# ConectoresAdicionales.net
KiCad netlist of a schematic drawn in Altium Designer
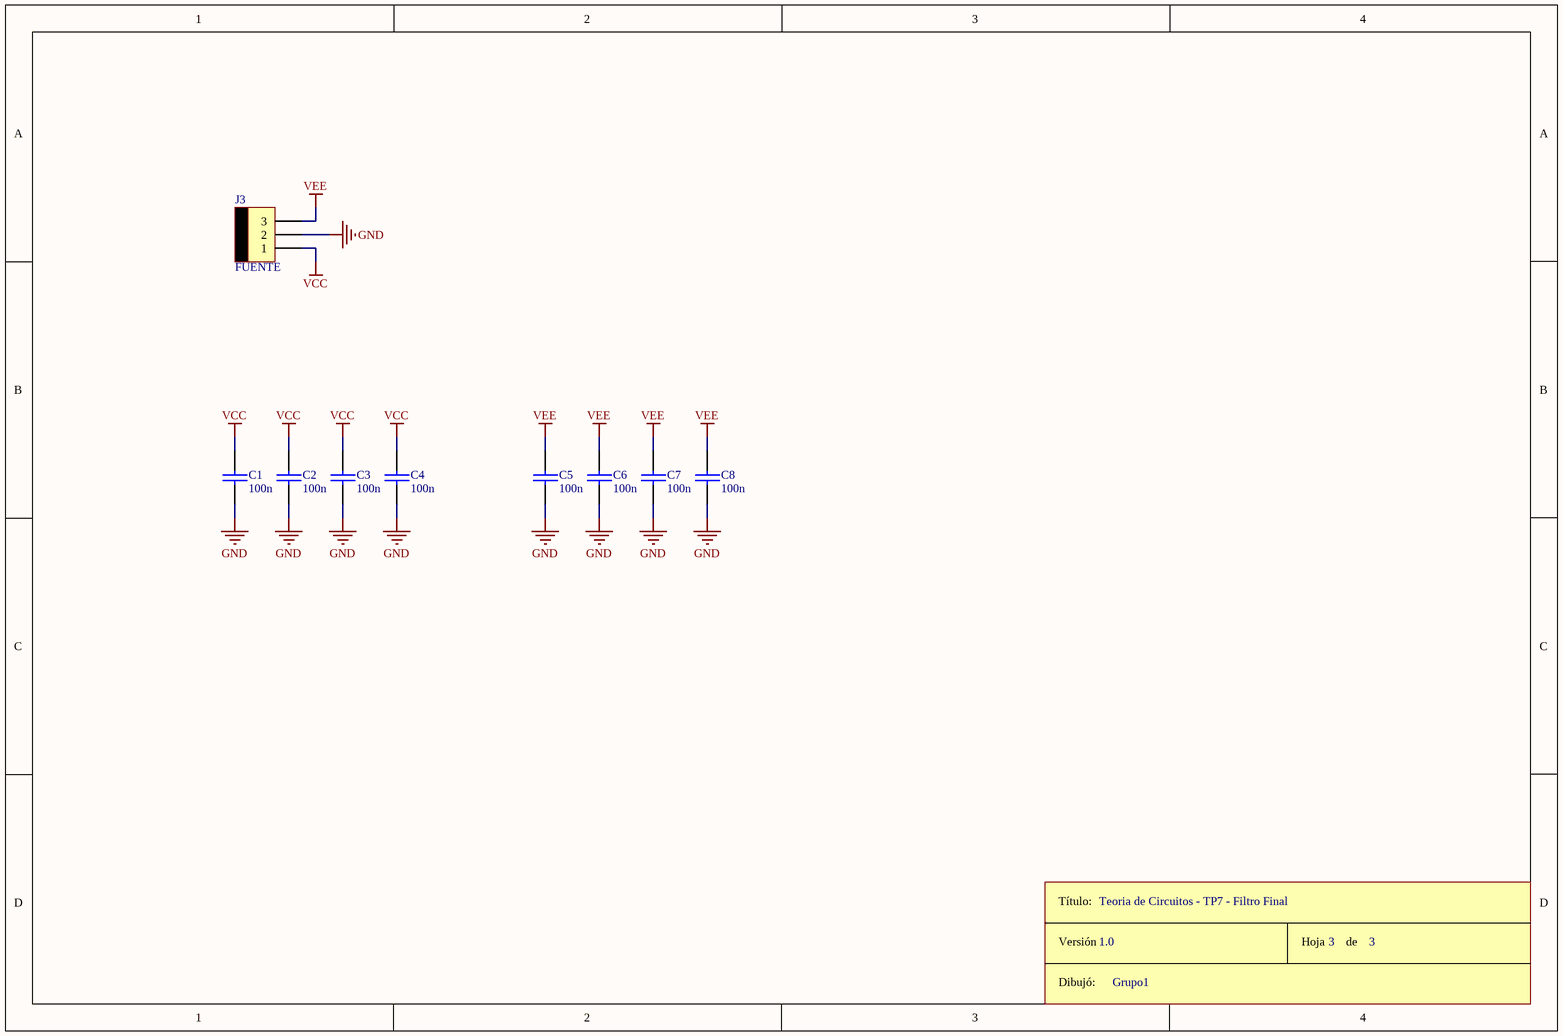
[diagram p0: ConectoresAdicionales.SchDoc]

(export (version "E")
  (design (tool "Eeschema 10.0.6"))
  (components
    (comp (ref "C1") (value "100n") (footprint "CAP100") (libsource (lib "LIB PIO IX") (part "CAP")))
    (comp (ref "C2") (value "100n") (footprint "CAP100") (libsource (lib "LIB PIO IX") (part "CAP")))
    (comp (ref "C3") (value "100n") (footprint "CAP100") (libsource (lib "LIB PIO IX") (part "CAP")))
    (comp (ref "C4") (value "100n") (footprint "CAP100") (libsource (lib "LIB PIO IX") (part "CAP")))
    (comp (ref "C5") (value "100n") (footprint "CAP100") (libsource (lib "LIB PIO IX") (part "CAP")))
    (comp (ref "C6") (value "100n") (footprint "CAP100") (libsource (lib "LIB PIO IX") (part "CAP")))
    (comp (ref "C7") (value "100n") (footprint "CAP100") (libsource (lib "LIB PIO IX") (part "CAP")))
    (comp (ref "C8") (value "100n") (footprint "CAP100") (libsource (lib "LIB PIO IX") (part "CAP")))
    (comp (ref "J3") (value "FUENTE") (footprint "MOLEX3") (libsource (lib "LIB PIO IX") (part "MOLEX3")))
    (comp (ref "ROT3") (value "Rótulo") (libsource (lib "LIB PIO IX") (part "Rótulo")))
  )
  (nets
    (net (code "1") (name "GND") (class "Default")
      (node (ref "C1") (pin "2") (pinfunction "2_2") (pintype "passive"))
      (node (ref "C2") (pin "2") (pinfunction "2_2") (pintype "passive"))
      (node (ref "C3") (pin "2") (pinfunction "2_2") (pintype "passive"))
      (node (ref "C4") (pin "2") (pinfunction "2_2") (pintype "passive"))
      (node (ref "C5") (pin "2") (pinfunction "2_2") (pintype "passive"))
      (node (ref "C6") (pin "2") (pinfunction "2_2") (pintype "passive"))
      (node (ref "C7") (pin "2") (pinfunction "2_2") (pintype "passive"))
      (node (ref "C8") (pin "2") (pinfunction "2_2") (pintype "passive"))
      (node (ref "J3") (pin "2") (pinfunction "2_2") (pintype "passive"))
    )
    (net (code "2") (name "VCC") (class "Default")
      (node (ref "C1") (pin "1") (pinfunction "1_1") (pintype "passive"))
      (node (ref "C2") (pin "1") (pinfunction "1_1") (pintype "passive"))
      (node (ref "C3") (pin "1") (pinfunction "1_1") (pintype "passive"))
      (node (ref "C4") (pin "1") (pinfunction "1_1") (pintype "passive"))
      (node (ref "J3") (pin "1") (pinfunction "1_1") (pintype "passive"))
    )
    (net (code "3") (name "VEE") (class "Default")
      (node (ref "C5") (pin "1") (pinfunction "1_1") (pintype "passive"))
      (node (ref "C6") (pin "1") (pinfunction "1_1") (pintype "passive"))
      (node (ref "C7") (pin "1") (pinfunction "1_1") (pintype "passive"))
      (node (ref "C8") (pin "1") (pinfunction "1_1") (pintype "passive"))
      (node (ref "J3") (pin "3") (pinfunction "3_3") (pintype "passive"))
    )
  )
)
